# BaseShieldBrainDuino24Nov2017.net
KiCad netlist of a schematic drawn in EAGLE
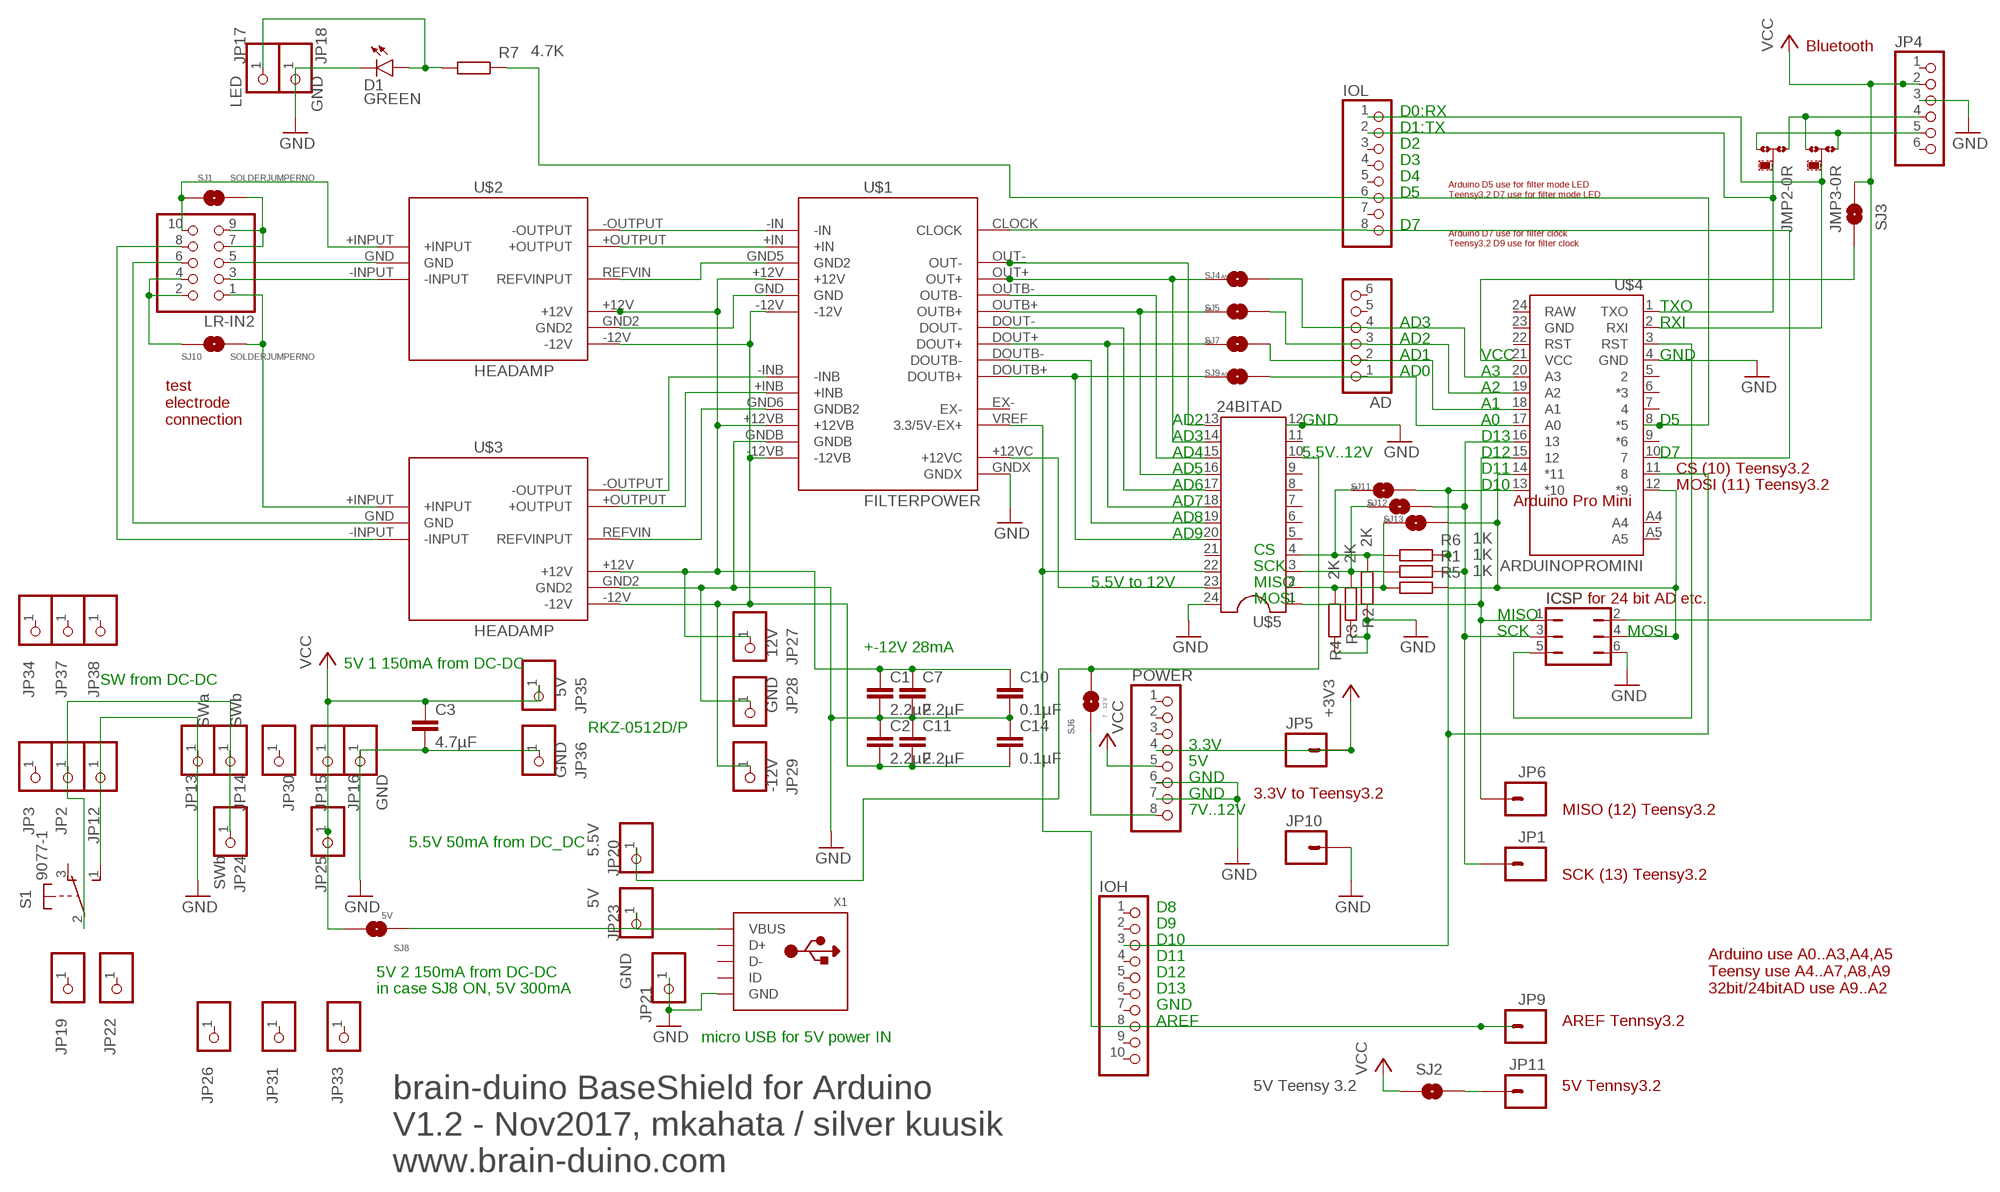
[diagram p0: schematic, sheet 1]

(export (version "E")
  (design (tool "Eeschema 10.0.6"))
  (components
    (comp (ref "AD")
      (value "PINHD-1X6")
      (footprint "eagle-import:1X06")
      (libsource (lib "eagle-import") (part "PINHD-1X6"))
    )
    (comp (ref "C1")
      (value "2.2µF")
      (footprint "eagle-import:C0402")
      (libsource (lib "eagle-import") (part "C-EUC0402"))
    )
    (comp (ref "C2")
      (value "2.2µF")
      (footprint "eagle-import:C0402")
      (libsource (lib "eagle-import") (part "C-EUC0402"))
    )
    (comp (ref "C3")
      (value "4.7µF")
      (footprint "eagle-import:C0402")
      (libsource (lib "eagle-import") (part "C-EUC0402"))
    )
    (comp (ref "C7")
      (value "2.2µF")
      (footprint "eagle-import:C0402")
      (libsource (lib "eagle-import") (part "C-EUC0402"))
    )
    (comp (ref "C10")
      (value "0.1µF")
      (footprint "eagle-import:C0402")
      (libsource (lib "eagle-import") (part "C-EUC0402"))
    )
    (comp (ref "C11")
      (value "2.2µF")
      (footprint "eagle-import:C0402")
      (libsource (lib "eagle-import") (part "C-EUC0402"))
    )
    (comp (ref "C14")
      (value "0.1µF")
      (footprint "eagle-import:C0402")
      (libsource (lib "eagle-import") (part "C-EUC0402"))
    )
    (comp (ref "D1")
      (value "GREEN")
      (footprint "eagle-import:LED-0603")
      (libsource (lib "eagle-import") (part "LED-GREEN0603"))
    )
    (comp (ref "ICSP")
      (value "JP3Q")
      (footprint "eagle-import:JP3Q")
      (libsource (lib "eagle-import") (part "JP3Q"))
    )
    (comp (ref "IOH")
      (value "PINHD-1X10")
      (footprint "eagle-import:1X10")
      (libsource (lib "eagle-import") (part "PINHD-1X10"))
    )
    (comp (ref "IOL")
      (value "PINHD-1X8")
      (footprint "eagle-import:1X08")
      (libsource (lib "eagle-import") (part "PINHD-1X8"))
    )
    (comp (ref "JMP2")
      (value "RX")
      (footprint "eagle-import:A0R-JMP")
      (libsource (lib "eagle-import") (part "0R-JUMPA"))
    )
    (comp (ref "JMP3")
      (value "TX")
      (footprint "eagle-import:A0R-JMP")
      (libsource (lib "eagle-import") (part "0R-JUMPA"))
    )
    (comp (ref "JP1")
      (value "M01PTH")
      (footprint "eagle-import:1X01")
      (libsource (lib "eagle-import") (part "M01PTH"))
    )
    (comp (ref "JP2")
      (value "PINHD-1X1")
      (footprint "eagle-import:1X01")
      (libsource (lib "eagle-import") (part "PINHD-1X1"))
    )
    (comp (ref "JP3")
      (value "PINHD-1X1")
      (footprint "eagle-import:1X01")
      (libsource (lib "eagle-import") (part "PINHD-1X1"))
    )
    (comp (ref "JP4")
      (value "PINHD-1X6")
      (footprint "eagle-import:1X06")
      (libsource (lib "eagle-import") (part "PINHD-1X6"))
    )
    (comp (ref "JP5")
      (value "M01PTH")
      (footprint "eagle-import:1X01")
      (libsource (lib "eagle-import") (part "M01PTH"))
    )
    (comp (ref "JP6")
      (value "M01PTH")
      (footprint "eagle-import:1X01")
      (libsource (lib "eagle-import") (part "M01PTH"))
    )
    (comp (ref "JP9")
      (value "M01PTH")
      (footprint "eagle-import:1X01")
      (libsource (lib "eagle-import") (part "M01PTH"))
    )
    (comp (ref "JP10")
      (value "M01PTH")
      (footprint "eagle-import:1X01")
      (libsource (lib "eagle-import") (part "M01PTH"))
    )
    (comp (ref "JP11")
      (value "M01PTH")
      (footprint "eagle-import:1X01")
      (libsource (lib "eagle-import") (part "M01PTH"))
    )
    (comp (ref "JP12")
      (value "PINHD-1X1")
      (footprint "eagle-import:1X01")
      (libsource (lib "eagle-import") (part "PINHD-1X1"))
    )
    (comp (ref "JP13")
      (value "SWa")
      (footprint "eagle-import:1X01")
      (libsource (lib "eagle-import") (part "PINHD-1X1"))
    )
    (comp (ref "JP14")
      (value "SWb")
      (footprint "eagle-import:1X01")
      (libsource (lib "eagle-import") (part "PINHD-1X1"))
    )
    (comp (ref "JP15")
      (value "+5V")
      (footprint "eagle-import:1X01")
      (libsource (lib "eagle-import") (part "PINHD-1X1"))
    )
    (comp (ref "JP16")
      (value "GND")
      (footprint "eagle-import:1X01")
      (libsource (lib "eagle-import") (part "PINHD-1X1"))
    )
    (comp (ref "JP17")
      (value "LED")
      (footprint "eagle-import:1X01")
      (libsource (lib "eagle-import") (part "PINHD-1X1"))
    )
    (comp (ref "JP18")
      (value "GND")
      (footprint "eagle-import:1X01")
      (libsource (lib "eagle-import") (part "PINHD-1X1"))
    )
    (comp (ref "JP19")
      (value "PINHD-1X1")
      (footprint "eagle-import:1X01")
      (libsource (lib "eagle-import") (part "PINHD-1X1"))
    )
    (comp (ref "JP20")
      (value "5.5V")
      (footprint "eagle-import:1X01")
      (libsource (lib "eagle-import") (part "PINHD-1X1"))
    )
    (comp (ref "JP21")
      (value "GND")
      (footprint "eagle-import:1X01")
      (libsource (lib "eagle-import") (part "PINHD-1X1"))
    )
    (comp (ref "JP22")
      (value "PINHD-1X1")
      (footprint "eagle-import:1X01")
      (libsource (lib "eagle-import") (part "PINHD-1X1"))
    )
    (comp (ref "JP23")
      (value "5V")
      (footprint "eagle-import:1X01")
      (libsource (lib "eagle-import") (part "PINHD-1X1"))
    )
    (comp (ref "JP24")
      (value "SWb")
      (footprint "eagle-import:1X01")
      (libsource (lib "eagle-import") (part "PINHD-1X1"))
    )
    (comp (ref "JP25")
      (value "+5V")
      (footprint "eagle-import:1X01")
      (libsource (lib "eagle-import") (part "PINHD-1X1"))
    )
    (comp (ref "JP26")
      (value "PINHD-1X1")
      (footprint "eagle-import:1X01")
      (libsource (lib "eagle-import") (part "PINHD-1X1"))
    )
    (comp (ref "JP27")
      (value "12V")
      (footprint "eagle-import:1X01")
      (libsource (lib "eagle-import") (part "PINHD-1X1"))
    )
    (comp (ref "JP28")
      (value "GND")
      (footprint "eagle-import:1X01")
      (libsource (lib "eagle-import") (part "PINHD-1X1"))
    )
    (comp (ref "JP29")
      (value "-12V")
      (footprint "eagle-import:1X01")
      (libsource (lib "eagle-import") (part "PINHD-1X1"))
    )
    (comp (ref "JP30")
      (value "PINHD-1X1")
      (footprint "eagle-import:1X01")
      (libsource (lib "eagle-import") (part "PINHD-1X1"))
    )
    (comp (ref "JP31")
      (value "PINHD-1X1")
      (footprint "eagle-import:1X01")
      (libsource (lib "eagle-import") (part "PINHD-1X1"))
    )
    (comp (ref "JP33")
      (value "PINHD-1X1")
      (footprint "eagle-import:1X01")
      (libsource (lib "eagle-import") (part "PINHD-1X1"))
    )
    (comp (ref "JP34")
      (value "PINHD-1X1")
      (footprint "eagle-import:1X01")
      (libsource (lib "eagle-import") (part "PINHD-1X1"))
    )
    (comp (ref "JP35")
      (value "5V")
      (footprint "eagle-import:1X01")
      (libsource (lib "eagle-import") (part "PINHD-1X1"))
    )
    (comp (ref "JP36")
      (value "GND")
      (footprint "eagle-import:1X01")
      (libsource (lib "eagle-import") (part "PINHD-1X1"))
    )
    (comp (ref "JP37")
      (value "PINHD-1X1")
      (footprint "eagle-import:1X01")
      (libsource (lib "eagle-import") (part "PINHD-1X1"))
    )
    (comp (ref "JP38")
      (value "PINHD-1X1")
      (footprint "eagle-import:1X01")
      (libsource (lib "eagle-import") (part "PINHD-1X1"))
    )
    (comp (ref "LR-IN2")
      (value "PINHD-2X5/90")
      (footprint "eagle-import:2X05_90")
      (libsource (lib "eagle-import") (part "PINHD-2X5/90"))
    )
    (comp (ref "POWER")
      (value "PINHD-1X8")
      (footprint "eagle-import:1X08")
      (libsource (lib "eagle-import") (part "PINHD-1X8"))
    )
    (comp (ref "R1")
      (value "1K")
      (footprint "eagle-import:R0402")
      (libsource (lib "eagle-import") (part "R-EU_R0402"))
    )
    (comp (ref "R2")
      (value "2K")
      (footprint "eagle-import:R0402")
      (libsource (lib "eagle-import") (part "R-EU_R0402"))
    )
    (comp (ref "R3")
      (value "2K")
      (footprint "eagle-import:R0402")
      (libsource (lib "eagle-import") (part "R-EU_R0402"))
    )
    (comp (ref "R4")
      (value "2K")
      (footprint "eagle-import:R0402")
      (libsource (lib "eagle-import") (part "R-EU_R0402"))
    )
    (comp (ref "R5")
      (value "1K")
      (footprint "eagle-import:R0402")
      (libsource (lib "eagle-import") (part "R-EU_R0402"))
    )
    (comp (ref "R6")
      (value "1K")
      (footprint "eagle-import:R0402")
      (libsource (lib "eagle-import") (part "R-EU_R0402"))
    )
    (comp (ref "R7")
      (value "4.7K")
      (footprint "eagle-import:R0402")
      (libsource (lib "eagle-import") (part "R-EU_R0402"))
    )
    (comp (ref "S1")
      (value "9077-1")
      (footprint "eagle-import:9077-1")
      (libsource (lib "eagle-import") (part "9077-1"))
    )
    (comp (ref "SJ1")
      (value "SOLDERJUMPERNO")
      (footprint "eagle-import:SJ_2S-NO")
      (libsource (lib "eagle-import") (part "SOLDERJUMPERNO"))
    )
    (comp (ref "SJ2")
      (value "5V Teensy 3.2")
      (footprint "eagle-import:SJ_2S-NO")
      (libsource (lib "eagle-import") (part "SOLDERJUMPERNO"))
    )
    (comp (ref "SJ3")
      (value "5V Arduino Pro Mini")
      (footprint "eagle-import:SJ_2S-NO")
      (libsource (lib "eagle-import") (part "SOLDERJUMPERNO"))
    )
    (comp (ref "SJ4")
      (value "A5")
      (footprint "eagle-import:SJ_2S-NO")
      (libsource (lib "eagle-import") (part "SOLDERJUMPERNO"))
    )
    (comp (ref "SJ5")
      (value "A4")
      (footprint "eagle-import:SJ_2S-NO")
      (libsource (lib "eagle-import") (part "SOLDERJUMPERNO"))
    )
    (comp (ref "SJ6")
      (value "7 .. 12 V")
      (footprint "eagle-import:SJ_2S-NO")
      (libsource (lib "eagle-import") (part "SOLDERJUMPERNO"))
    )
    (comp (ref "SJ7")
      (value "A2")
      (footprint "eagle-import:SJ_2S-NO")
      (libsource (lib "eagle-import") (part "SOLDERJUMPERNO"))
    )
    (comp (ref "SJ8")
      (value "5V")
      (footprint "eagle-import:SJ_2S-NO")
      (libsource (lib "eagle-import") (part "SOLDERJUMPERNO"))
    )
    (comp (ref "SJ9")
      (value "A0")
      (footprint "eagle-import:SJ_2S-NO")
      (libsource (lib "eagle-import") (part "SOLDERJUMPERNO"))
    )
    (comp (ref "SJ10")
      (value "SOLDERJUMPERNO")
      (footprint "eagle-import:SJ_2S-NO")
      (libsource (lib "eagle-import") (part "SOLDERJUMPERNO"))
    )
    (comp (ref "SJ11")
      (value "A4")
      (footprint "eagle-import:SJ_2S-NO")
      (libsource (lib "eagle-import") (part "SOLDERJUMPERNO"))
    )
    (comp (ref "SJ12")
      (value "A4")
      (footprint "eagle-import:SJ_2S-NO")
      (libsource (lib "eagle-import") (part "SOLDERJUMPERNO"))
    )
    (comp (ref "SJ13")
      (value "A4")
      (footprint "eagle-import:SJ_2S-NO")
      (libsource (lib "eagle-import") (part "SOLDERJUMPERNO"))
    )
    (comp (ref "U$1")
      (value "FILTERPOWER")
      (footprint "eagle-import:FILTERPOWER")
      (libsource (lib "eagle-import") (part "FILTERPOWER"))
    )
    (comp (ref "U$2")
      (value "HEADAMP")
      (footprint "eagle-import:HEADAMP")
      (libsource (lib "eagle-import") (part "HEADAMP"))
    )
    (comp (ref "U$3")
      (value "HEADAMP")
      (footprint "eagle-import:HEADAMP")
      (libsource (lib "eagle-import") (part "HEADAMP"))
    )
    (comp (ref "U$4")
      (value "ARDUINOPROMINI")
      (footprint "eagle-import:ARDUINOPROMINI")
      (libsource (lib "eagle-import") (part "ARDUINOPROMINI"))
    )
    (comp (ref "U$5")
      (value "24BITAD")
      (footprint "eagle-import:24BITAD")
      (libsource (lib "eagle-import") (part "24BITAD"))
    )
    (comp (ref "X1")
      (value "USB_MICRO_20329_V2")
      (footprint "eagle-import:4UCONN_20329_V2")
      (libsource (lib "eagle-import") (part "USB_MICRO_20329_V2"))
    )
  )
  (nets
    (net (code "1") (name "+3V3") (class "Default")
      (node (ref "JP5") (pin "1") (pinfunction "1_1") (pintype "passive"))
      (node (ref "POWER") (pin "4") (pinfunction "4_4") (pintype "passive"))
    )
    (net (code "2") (name "GND") (class "Default")
      (node (ref "C1") (pin "2") (pinfunction "2_2") (pintype "passive"))
      (node (ref "C10") (pin "2") (pinfunction "2_2") (pintype "passive"))
      (node (ref "C11") (pin "1") (pinfunction "1_1") (pintype "passive"))
      (node (ref "C14") (pin "1") (pinfunction "1_1") (pintype "passive"))
      (node (ref "C2") (pin "1") (pinfunction "1_1") (pintype "passive"))
      (node (ref "C3") (pin "2") (pinfunction "2_2") (pintype "passive"))
      (node (ref "C7") (pin "2") (pinfunction "2_2") (pintype "passive"))
      (node (ref "D1") (pin "C") (pinfunction "C_C") (pintype "passive"))
      (node (ref "ICSP") (pin "6") (pinfunction "6_6") (pintype "passive"))
      (node (ref "JP10") (pin "1") (pinfunction "1_1") (pintype "passive"))
      (node (ref "JP12") (pin "1") (pinfunction "1_1") (pintype "passive"))
      (node (ref "JP13") (pin "1") (pinfunction "1_1") (pintype "passive"))
      (node (ref "JP16") (pin "1") (pinfunction "1_1") (pintype "passive"))
      (node (ref "JP18") (pin "1") (pinfunction "1_1") (pintype "passive"))
      (node (ref "JP21") (pin "1") (pinfunction "1_1") (pintype "passive"))
      (node (ref "JP28") (pin "1") (pinfunction "1_1") (pintype "passive"))
      (node (ref "JP36") (pin "1") (pinfunction "1_1") (pintype "passive"))
      (node (ref "JP4") (pin "3") (pinfunction "3_3") (pintype "passive"))
      (node (ref "POWER") (pin "6") (pinfunction "6_6") (pintype "passive"))
      (node (ref "POWER") (pin "7") (pinfunction "7_7") (pintype "passive"))
      (node (ref "R2") (pin "1") (pinfunction "1_1") (pintype "passive"))
      (node (ref "R3") (pin "1") (pinfunction "1_1") (pintype "passive"))
      (node (ref "R4") (pin "1") (pinfunction "1_1") (pintype "passive"))
      (node (ref "S1") (pin "1") (pinfunction "S_1") (pintype "passive"))
      (node (ref "U$1") (pin "GNDB") (pinfunction "GNDB_GNDB") (pintype "power_in"))
      (node (ref "U$1") (pin "GNDX") (pinfunction "GNDX_GNDX") (pintype "power_in"))
      (node (ref "U$3") (pin "GND2") (pinfunction "GND2_GND2") (pintype "bidirectional"))
      (node (ref "U$4") (pin "4") (pinfunction "GND_4") (pintype "bidirectional"))
      (node (ref "U$5") (pin "12") (pinfunction "12_12") (pintype "passive"))
      (node (ref "U$5") (pin "24") (pinfunction "24_24") (pintype "passive"))
      (node (ref "X1") (pin "BASE@1") (pinfunction "GND_BASE@1") (pintype "power_in"))
      (node (ref "X1") (pin "BASE@2") (pinfunction "GND_BASE@2") (pintype "power_in"))
      (node (ref "X1") (pin "GND") (pinfunction "GND_GND") (pintype "power_in"))
      (node (ref "X1") (pin "SPRT@1") (pinfunction "GND_SPRT@1") (pintype "power_in"))
      (node (ref "X1") (pin "SPRT@2") (pinfunction "GND_SPRT@2") (pintype "power_in"))
      (node (ref "X1") (pin "SPRT@3") (pinfunction "GND_SPRT@3") (pintype "power_in"))
      (node (ref "X1") (pin "SPRT@4") (pinfunction "GND_SPRT@4") (pintype "power_in"))
    )
    (net (code "3") (name "Net-(C1-Pad1)") (class "Default")
      (node (ref "C1") (pin "1") (pinfunction "1_1") (pintype "passive"))
      (node (ref "C10") (pin "1") (pinfunction "1_1") (pintype "passive"))
      (node (ref "C7") (pin "1") (pinfunction "1_1") (pintype "passive"))
      (node (ref "JP27") (pin "1") (pinfunction "1_1") (pintype "passive"))
      (node (ref "U$1") (pin "+12V") (pinfunction "+12V_+12V") (pintype "bidirectional"))
      (node (ref "U$1") (pin "+12VB") (pinfunction "+12VB_+12VB") (pintype "bidirectional"))
      (node (ref "U$2") (pin "+12V") (pinfunction "+12V_+12V") (pintype "bidirectional"))
      (node (ref "U$3") (pin "+12V") (pinfunction "+12V_+12V") (pintype "bidirectional"))
    )
    (net (code "4") (name "Net-(C11-Pad2)") (class "Default")
      (node (ref "C11") (pin "2") (pinfunction "2_2") (pintype "passive"))
      (node (ref "C14") (pin "2") (pinfunction "2_2") (pintype "passive"))
      (node (ref "C2") (pin "2") (pinfunction "2_2") (pintype "passive"))
      (node (ref "JP29") (pin "1") (pinfunction "1_1") (pintype "passive"))
      (node (ref "U$1") (pin "-12V") (pinfunction "-12V_-12V") (pintype "bidirectional"))
      (node (ref "U$1") (pin "-12VB") (pinfunction "-12VB_-12VB") (pintype "bidirectional"))
      (node (ref "U$2") (pin "-12V") (pinfunction "-12V_-12V") (pintype "bidirectional"))
      (node (ref "U$3") (pin "-12V") (pinfunction "-12V_-12V") (pintype "bidirectional"))
    )
    (net (code "5") (name "Net-(D1-PadA)") (class "Default")
      (node (ref "D1") (pin "A") (pinfunction "A_A") (pintype "passive"))
      (node (ref "JP17") (pin "1") (pinfunction "1_1") (pintype "passive"))
      (node (ref "R7") (pin "1") (pinfunction "1_1") (pintype "passive"))
    )
    (net (code "6") (name "Net-(ICSP-Pad5)") (class "Default")
      (node (ref "ICSP") (pin "5") (pinfunction "5_5") (pintype "passive"))
      (node (ref "U$4") (pin "3") (pinfunction "RST_3") (pintype "bidirectional"))
    )
    (net (code "7") (name "Net-(JMP2-Pad1)") (class "Default")
      (node (ref "JMP2") (pin "1") (pinfunction "1_1") (pintype "passive"))
      (node (ref "JMP3") (pin "3") (pinfunction "3_3") (pintype "passive"))
      (node (ref "JP4") (pin "4") (pinfunction "4_4") (pintype "passive"))
    )
    (net (code "8") (name "Net-(JMP2-Pad3)") (class "Default")
      (node (ref "JMP2") (pin "3") (pinfunction "3_3") (pintype "passive"))
      (node (ref "JMP3") (pin "1") (pinfunction "1_1") (pintype "passive"))
      (node (ref "JP4") (pin "5") (pinfunction "5_5") (pintype "passive"))
    )
    (net (code "9") (name "Net-(JP11-Pad1)") (class "Default")
      (node (ref "JP11") (pin "1") (pinfunction "1_1") (pintype "passive"))
      (node (ref "SJ2") (pin "2") (pinfunction "2_2") (pintype "passive"))
    )
    (net (code "10") (name "Net-(JP20-Pad1)") (class "Default")
      (node (ref "JP20") (pin "1") (pinfunction "1_1") (pintype "passive"))
      (node (ref "SJ6") (pin "2") (pinfunction "2_2") (pintype "passive"))
      (node (ref "U$5") (pin "10") (pinfunction "10_10") (pintype "passive"))
    )
    (net (code "11") (name "Net-(JP23-Pad1)") (class "Default")
      (node (ref "JP23") (pin "1") (pinfunction "1_1") (pintype "passive"))
      (node (ref "SJ8") (pin "1") (pinfunction "1_1") (pintype "passive"))
      (node (ref "X1") (pin "VBUS") (pinfunction "VBUS_VBUS") (pintype "power_in"))
    )
    (net (code "12") (name "Net-(LR-IN2-Pad1)") (class "Default")
      (node (ref "LR-IN2") (pin "1") (pinfunction "1_1") (pintype "passive"))
      (node (ref "SJ10") (pin "2") (pinfunction "2_2") (pintype "passive"))
      (node (ref "U$3") (pin "+INPUT") (pinfunction "+INPUT_+INPUT") (pintype "bidirectional"))
    )
    (net (code "13") (name "Net-(LR-IN2-Pad2)") (class "Default")
      (node (ref "LR-IN2") (pin "2") (pinfunction "2_2") (pintype "passive"))
      (node (ref "LR-IN2") (pin "4") (pinfunction "4_4") (pintype "passive"))
      (node (ref "SJ10") (pin "1") (pinfunction "1_1") (pintype "passive"))
    )
    (net (code "14") (name "Net-(LR-IN2-Pad3)") (class "Default")
      (node (ref "LR-IN2") (pin "3") (pinfunction "3_3") (pintype "passive"))
      (node (ref "U$2") (pin "-INPUT") (pinfunction "-INPUT_-INPUT") (pintype "bidirectional"))
    )
    (net (code "15") (name "Net-(LR-IN2-Pad5)") (class "Default")
      (node (ref "LR-IN2") (pin "5") (pinfunction "5_5") (pintype "passive"))
      (node (ref "U$2") (pin "GND") (pinfunction "GND_GND") (pintype "bidirectional"))
    )
    (net (code "16") (name "Net-(LR-IN2-Pad6)") (class "Default")
      (node (ref "LR-IN2") (pin "6") (pinfunction "6_6") (pintype "passive"))
      (node (ref "U$3") (pin "GND") (pinfunction "GND_GND") (pintype "bidirectional"))
    )
    (net (code "17") (name "Net-(LR-IN2-Pad7)") (class "Default")
      (node (ref "LR-IN2") (pin "7") (pinfunction "7_7") (pintype "passive"))
      (node (ref "LR-IN2") (pin "9") (pinfunction "9_9") (pintype "passive"))
      (node (ref "SJ1") (pin "2") (pinfunction "2_2") (pintype "passive"))
    )
    (net (code "18") (name "Net-(LR-IN2-Pad8)") (class "Default")
      (node (ref "LR-IN2") (pin "8") (pinfunction "8_8") (pintype "passive"))
      (node (ref "U$3") (pin "-INPUT") (pinfunction "-INPUT_-INPUT") (pintype "bidirectional"))
    )
    (net (code "19") (name "Net-(LR-IN2-Pad10)") (class "Default")
      (node (ref "LR-IN2") (pin "10") (pinfunction "10_10") (pintype "passive"))
      (node (ref "SJ1") (pin "1") (pinfunction "1_1") (pintype "passive"))
      (node (ref "U$2") (pin "+INPUT") (pinfunction "+INPUT_+INPUT") (pintype "bidirectional"))
    )
    (net (code "20") (name "Net-(POWER-Pad8)") (class "Default")
      (node (ref "POWER") (pin "8") (pinfunction "8_8") (pintype "passive"))
      (node (ref "SJ6") (pin "1") (pinfunction "1_1") (pintype "passive"))
    )
    (net (code "21") (name "Net-(R1-Pad1)") (class "Default")
      (node (ref "R1") (pin "1") (pinfunction "1_1") (pintype "passive"))
      (node (ref "R3") (pin "2") (pinfunction "2_2") (pintype "passive"))
      (node (ref "SJ12") (pin "1") (pinfunction "1_1") (pintype "passive"))
      (node (ref "U$5") (pin "3") (pinfunction "3_3") (pintype "passive"))
    )
    (net (code "22") (name "Net-(R2-Pad2)") (class "Default")
      (node (ref "R2") (pin "2") (pinfunction "2_2") (pintype "passive"))
      (node (ref "R6") (pin "1") (pinfunction "1_1") (pintype "passive"))
      (node (ref "SJ11") (pin "1") (pinfunction "1_1") (pintype "passive"))
      (node (ref "U$5") (pin "4") (pinfunction "4_4") (pintype "passive"))
    )
    (net (code "23") (name "Net-(R4-Pad2)") (class "Default")
      (node (ref "R4") (pin "2") (pinfunction "2_2") (pintype "passive"))
      (node (ref "R5") (pin "1") (pinfunction "1_1") (pintype "passive"))
      (node (ref "SJ13") (pin "1") (pinfunction "1_1") (pintype "passive"))
      (node (ref "U$5") (pin "2") (pinfunction "2_2") (pintype "passive"))
    )
    (net (code "24") (name "Net-(S1-P)") (class "Default")
      (node (ref "JP14") (pin "1") (pinfunction "1_1") (pintype "passive"))
      (node (ref "JP2") (pin "1") (pinfunction "1_1") (pintype "passive"))
      (node (ref "JP24") (pin "1") (pinfunction "1_1") (pintype "passive"))
      (node (ref "S1") (pin "2") (pinfunction "P_2") (pintype "passive"))
    )
    (net (code "25") (name "Net-(SJ4-Pad1)") (class "Default")
      (node (ref "SJ4") (pin "1") (pinfunction "1_1") (pintype "passive"))
      (node (ref "U$1") (pin "OUT+") (pinfunction "OUT+_OUT+") (pintype "power_in"))
      (node (ref "U$5") (pin "14") (pinfunction "14_14") (pintype "passive"))
    )
    (net (code "26") (name "Net-(SJ5-Pad1)") (class "Default")
      (node (ref "SJ5") (pin "1") (pinfunction "1_1") (pintype "passive"))
      (node (ref "U$1") (pin "OUTB+") (pinfunction "OUTB+_OUTB+") (pintype "power_in"))
      (node (ref "U$5") (pin "16") (pinfunction "16_16") (pintype "passive"))
    )
    (net (code "27") (name "Net-(SJ7-Pad1)") (class "Default")
      (node (ref "SJ7") (pin "1") (pinfunction "1_1") (pintype "passive"))
      (node (ref "U$1") (pin "DOUT+") (pinfunction "DOUT+_DOUT+") (pintype "output"))
      (node (ref "U$5") (pin "18") (pinfunction "18_18") (pintype "passive"))
    )
    (net (code "28") (name "Net-(SJ9-Pad1)") (class "Default")
      (node (ref "SJ9") (pin "1") (pinfunction "1_1") (pintype "passive"))
      (node (ref "U$1") (pin "DOUTB+") (pinfunction "DOUTB+_DOUTB+") (pintype "output"))
      (node (ref "U$5") (pin "20") (pinfunction "20_20") (pintype "passive"))
    )
    (net (code "29") (name "Net-(U$1-3.3{slash}5V-EX+)") (class "Default")
      (node (ref "IOH") (pin "8") (pinfunction "8_8") (pintype "passive"))
      (node (ref "JP9") (pin "1") (pinfunction "1_1") (pintype "passive"))
      (node (ref "U$1") (pin "VREF") (pinfunction "3.3/5V-EX+_VREF") (pintype "output"))
      (node (ref "U$5") (pin "22") (pinfunction "22_22") (pintype "passive"))
    )
    (net (code "30") (name "Net-(U$1-GND2)") (class "Default")
      (node (ref "U$1") (pin "GND5") (pinfunction "GND2_GND5") (pintype "power_in"))
      (node (ref "U$2") (pin "REFVIN") (pinfunction "REFVINPUT_REFVIN") (pintype "bidirectional"))
    )
    (net (code "31") (name "Net-(U$1-GNDB2)") (class "Default")
      (node (ref "U$1") (pin "GND6") (pinfunction "GNDB2_GND6") (pintype "power_in"))
      (node (ref "U$3") (pin "REFVIN") (pinfunction "REFVINPUT_REFVIN") (pintype "bidirectional"))
    )
    (net (code "32") (name "Net-(U$1-Pad+12VC)") (class "Default")
      (node (ref "U$1") (pin "+12VC") (pinfunction "+12VC_+12VC") (pintype "power_in"))
      (node (ref "U$5") (pin "23") (pinfunction "23_23") (pintype "passive"))
    )
    (net (code "33") (name "Net-(U$1-Pad+IN)") (class "Default")
      (node (ref "U$1") (pin "+IN") (pinfunction "+IN_+IN") (pintype "input"))
      (node (ref "U$2") (pin "+OUTPUT") (pinfunction "+OUTPUT_+OUTPUT") (pintype "bidirectional"))
    )
    (net (code "34") (name "Net-(U$1-Pad+INB)") (class "Default")
      (node (ref "U$1") (pin "+INB") (pinfunction "+INB_+INB") (pintype "bidirectional"))
      (node (ref "U$3") (pin "+OUTPUT") (pinfunction "+OUTPUT_+OUTPUT") (pintype "bidirectional"))
    )
    (net (code "35") (name "Net-(U$1-Pad-IN)") (class "Default")
      (node (ref "U$1") (pin "-IN") (pinfunction "-IN_-IN") (pintype "input"))
      (node (ref "U$2") (pin "-OUTPUT") (pinfunction "-OUTPUT_-OUTPUT") (pintype "bidirectional"))
    )
    (net (code "36") (name "Net-(U$1-Pad-INB)") (class "Default")
      (node (ref "U$1") (pin "-INB") (pinfunction "-INB_-INB") (pintype "bidirectional"))
      (node (ref "U$3") (pin "-OUTPUT") (pinfunction "-OUTPUT_-OUTPUT") (pintype "bidirectional"))
    )
    (net (code "37") (name "Net-(U$1-PadDOUT-)") (class "Default")
      (node (ref "U$1") (pin "DOUT-") (pinfunction "DOUT-_DOUT-") (pintype "output"))
      (node (ref "U$5") (pin "17") (pinfunction "17_17") (pintype "passive"))
    )
    (net (code "38") (name "Net-(U$1-PadDOUTB-)") (class "Default")
      (node (ref "U$1") (pin "DOUTB-") (pinfunction "DOUTB-_DOUTB-") (pintype "output"))
      (node (ref "U$5") (pin "19") (pinfunction "19_19") (pintype "passive"))
    )
    (net (code "39") (name "Net-(U$1-PadGND)") (class "Default")
      (node (ref "U$1") (pin "GND") (pinfunction "GND_GND") (pintype "power_in"))
      (node (ref "U$2") (pin "GND2") (pinfunction "GND2_GND2") (pintype "bidirectional"))
    )
    (net (code "40") (name "Net-(U$1-PadOUT-)") (class "Default")
      (node (ref "U$1") (pin "OUT-") (pinfunction "OUT-_OUT-") (pintype "bidirectional"))
      (node (ref "U$5") (pin "13") (pinfunction "13_13") (pintype "passive"))
    )
    (net (code "41") (name "Net-(U$1-PadOUTB-)") (class "Default")
      (node (ref "U$1") (pin "OUTB-") (pinfunction "OUTB-_OUTB-") (pintype "output"))
      (node (ref "U$5") (pin "15") (pinfunction "15_15") (pintype "passive"))
    )
    (net (code "42") (name "Net-(U$4-*5)") (class "Default")
      (node (ref "IOL") (pin "6") (pinfunction "6_6") (pintype "passive"))
      (node (ref "R7") (pin "2") (pinfunction "2_2") (pintype "passive"))
      (node (ref "U$4") (pin "8") (pinfunction "*5_8") (pintype "bidirectional"))
    )
    (net (code "43") (name "Net-(U$4-*10)") (class "Default")
      (node (ref "IOH") (pin "3") (pinfunction "3_3") (pintype "passive"))
      (node (ref "R6") (pin "2") (pinfunction "2_2") (pintype "passive"))
      (node (ref "SJ11") (pin "2") (pinfunction "2_2") (pintype "passive"))
      (node (ref "U$4") (pin "11") (pinfunction "8_11") (pintype "bidirectional"))
      (node (ref "U$4") (pin "13") (pinfunction "*10_13") (pintype "bidirectional"))
    )
    (net (code "44") (name "Net-(U$4-*11)") (class "Default")
      (node (ref "ICSP") (pin "4") (pinfunction "4_4") (pintype "passive"))
      (node (ref "R5") (pin "2") (pinfunction "2_2") (pintype "passive"))
      (node (ref "SJ13") (pin "2") (pinfunction "2_2") (pintype "passive"))
      (node (ref "U$4") (pin "12") (pinfunction "*9_12") (pintype "bidirectional"))
      (node (ref "U$4") (pin "14") (pinfunction "*11_14") (pintype "bidirectional"))
    )
    (net (code "45") (name "Net-(U$4-7)") (class "Default")
      (node (ref "IOL") (pin "8") (pinfunction "8_8") (pintype "passive"))
      (node (ref "U$1") (pin "CLOCK") (pinfunction "CLOCK_CLOCK") (pintype "input"))
      (node (ref "U$4") (pin "10") (pinfunction "7_10") (pintype "bidirectional"))
    )
    (net (code "46") (name "Net-(U$4-12)") (class "Default")
      (node (ref "ICSP") (pin "1") (pinfunction "1_1") (pintype "passive"))
      (node (ref "JP6") (pin "1") (pinfunction "1_1") (pintype "passive"))
      (node (ref "U$4") (pin "15") (pinfunction "12_15") (pintype "bidirectional"))
      (node (ref "U$5") (pin "1") (pinfunction "1_1") (pintype "passive"))
    )
    (net (code "47") (name "Net-(U$4-13)") (class "Default")
      (node (ref "ICSP") (pin "3") (pinfunction "3_3") (pintype "passive"))
      (node (ref "JP1") (pin "1") (pinfunction "1_1") (pintype "passive"))
      (node (ref "R1") (pin "2") (pinfunction "2_2") (pintype "passive"))
      (node (ref "SJ12") (pin "2") (pinfunction "2_2") (pintype "passive"))
      (node (ref "U$4") (pin "16") (pinfunction "13_16") (pintype "bidirectional"))
    )
    (net (code "48") (name "Net-(U$4-A0)") (class "Default")
      (node (ref "AD") (pin "1") (pinfunction "1_1") (pintype "passive"))
      (node (ref "SJ9") (pin "2") (pinfunction "2_2") (pintype "passive"))
      (node (ref "U$4") (pin "17") (pinfunction "A0_17") (pintype "bidirectional"))
    )
    (net (code "49") (name "Net-(U$4-A1)") (class "Default")
      (node (ref "AD") (pin "2") (pinfunction "2_2") (pintype "passive"))
      (node (ref "SJ7") (pin "2") (pinfunction "2_2") (pintype "passive"))
      (node (ref "U$4") (pin "18") (pinfunction "A1_18") (pintype "bidirectional"))
    )
    (net (code "50") (name "Net-(U$4-A2)") (class "Default")
      (node (ref "AD") (pin "3") (pinfunction "3_3") (pintype "passive"))
      (node (ref "SJ5") (pin "2") (pinfunction "2_2") (pintype "passive"))
      (node (ref "U$4") (pin "19") (pinfunction "A2_19") (pintype "bidirectional"))
    )
    (net (code "51") (name "Net-(U$4-A3)") (class "Default")
      (node (ref "AD") (pin "4") (pinfunction "4_4") (pintype "passive"))
      (node (ref "SJ4") (pin "2") (pinfunction "2_2") (pintype "passive"))
      (node (ref "U$4") (pin "20") (pinfunction "A3_20") (pintype "bidirectional"))
    )
    (net (code "52") (name "Net-(U$4-RXI)") (class "Default")
      (node (ref "IOL") (pin "1") (pinfunction "1_1") (pintype "passive"))
      (node (ref "JMP3") (pin "2") (pinfunction "2_2") (pintype "passive"))
      (node (ref "U$4") (pin "2") (pinfunction "RXI_2") (pintype "bidirectional"))
    )
    (net (code "53") (name "Net-(U$4-TXO)") (class "Default")
      (node (ref "IOL") (pin "2") (pinfunction "2_2") (pintype "passive"))
      (node (ref "JMP2") (pin "2") (pinfunction "2_2") (pintype "passive"))
      (node (ref "U$4") (pin "1") (pinfunction "TXO_1") (pintype "bidirectional"))
    )
    (net (code "54") (name "Net-(U$4-VCC)") (class "Default")
      (node (ref "SJ3") (pin "1") (pinfunction "1_1") (pintype "passive"))
      (node (ref "U$4") (pin "21") (pinfunction "VCC_21") (pintype "bidirectional"))
    )
    (net (code "55") (name "VCC") (class "Default")
      (node (ref "C3") (pin "1") (pinfunction "1_1") (pintype "passive"))
      (node (ref "ICSP") (pin "2") (pinfunction "2_2") (pintype "passive"))
      (node (ref "JP15") (pin "1") (pinfunction "1_1") (pintype "passive"))
      (node (ref "JP25") (pin "1") (pinfunction "1_1") (pintype "passive"))
      (node (ref "JP35") (pin "1") (pinfunction "1_1") (pintype "passive"))
      (node (ref "JP4") (pin "2") (pinfunction "2_2") (pintype "passive"))
      (node (ref "POWER") (pin "5") (pinfunction "5_5") (pintype "passive"))
      (node (ref "SJ2") (pin "1") (pinfunction "1_1") (pintype "passive"))
      (node (ref "SJ3") (pin "2") (pinfunction "2_2") (pintype "passive"))
      (node (ref "SJ8") (pin "2") (pinfunction "2_2") (pintype "passive"))
    )
    (net (code "56") (name "unconnected-(AD-Pad5)") (class "Default")
      (node (ref "AD") (pin "5") (pinfunction "5_5") (pintype "passive"))
    )
    (net (code "57") (name "unconnected-(AD-Pad6)") (class "Default")
      (node (ref "AD") (pin "6") (pinfunction "6_6") (pintype "passive"))
    )
    (net (code "58") (name "unconnected-(IOH-Pad1)") (class "Default")
      (node (ref "IOH") (pin "1") (pinfunction "1_1") (pintype "passive"))
    )
    (net (code "59") (name "unconnected-(IOH-Pad2)") (class "Default")
      (node (ref "IOH") (pin "2") (pinfunction "2_2") (pintype "passive"))
    )
    (net (code "60") (name "unconnected-(IOH-Pad4)") (class "Default")
      (node (ref "IOH") (pin "4") (pinfunction "4_4") (pintype "passive"))
    )
    (net (code "61") (name "unconnected-(IOH-Pad5)") (class "Default")
      (node (ref "IOH") (pin "5") (pinfunction "5_5") (pintype "passive"))
    )
    (net (code "62") (name "unconnected-(IOH-Pad6)") (class "Default")
      (node (ref "IOH") (pin "6") (pinfunction "6_6") (pintype "passive"))
    )
    (net (code "63") (name "unconnected-(IOH-Pad7)") (class "Default")
      (node (ref "IOH") (pin "7") (pinfunction "7_7") (pintype "passive"))
    )
    (net (code "64") (name "unconnected-(IOH-Pad9)") (class "Default")
      (node (ref "IOH") (pin "9") (pinfunction "9_9") (pintype "passive"))
    )
    (net (code "65") (name "unconnected-(IOH-Pad10)") (class "Default")
      (node (ref "IOH") (pin "10") (pinfunction "10_10") (pintype "passive"))
    )
    (net (code "66") (name "unconnected-(IOL-Pad3)") (class "Default")
      (node (ref "IOL") (pin "3") (pinfunction "3_3") (pintype "passive"))
    )
    (net (code "67") (name "unconnected-(IOL-Pad4)") (class "Default")
      (node (ref "IOL") (pin "4") (pinfunction "4_4") (pintype "passive"))
    )
    (net (code "68") (name "unconnected-(IOL-Pad5)") (class "Default")
      (node (ref "IOL") (pin "5") (pinfunction "5_5") (pintype "passive"))
    )
    (net (code "69") (name "unconnected-(IOL-Pad7)") (class "Default")
      (node (ref "IOL") (pin "7") (pinfunction "7_7") (pintype "passive"))
    )
    (net (code "70") (name "unconnected-(JP3-Pad1)") (class "Default")
      (node (ref "JP3") (pin "1") (pinfunction "1_1") (pintype "passive"))
    )
    (net (code "71") (name "unconnected-(JP4-Pad1)") (class "Default")
      (node (ref "JP4") (pin "1") (pinfunction "1_1") (pintype "passive"))
    )
    (net (code "72") (name "unconnected-(JP4-Pad6)") (class "Default")
      (node (ref "JP4") (pin "6") (pinfunction "6_6") (pintype "passive"))
    )
    (net (code "73") (name "unconnected-(JP19-Pad1)") (class "Default")
      (node (ref "JP19") (pin "1") (pinfunction "1_1") (pintype "passive"))
    )
    (net (code "74") (name "unconnected-(JP22-Pad1)") (class "Default")
      (node (ref "JP22") (pin "1") (pinfunction "1_1") (pintype "passive"))
    )
    (net (code "75") (name "unconnected-(JP26-Pad1)") (class "Default")
      (node (ref "JP26") (pin "1") (pinfunction "1_1") (pintype "passive"))
    )
    (net (code "76") (name "unconnected-(JP30-Pad1)") (class "Default")
      (node (ref "JP30") (pin "1") (pinfunction "1_1") (pintype "passive"))
    )
    (net (code "77") (name "unconnected-(JP31-Pad1)") (class "Default")
      (node (ref "JP31") (pin "1") (pinfunction "1_1") (pintype "passive"))
    )
    (net (code "78") (name "unconnected-(JP33-Pad1)") (class "Default")
      (node (ref "JP33") (pin "1") (pinfunction "1_1") (pintype "passive"))
    )
    (net (code "79") (name "unconnected-(JP34-Pad1)") (class "Default")
      (node (ref "JP34") (pin "1") (pinfunction "1_1") (pintype "passive"))
    )
    (net (code "80") (name "unconnected-(JP37-Pad1)") (class "Default")
      (node (ref "JP37") (pin "1") (pinfunction "1_1") (pintype "passive"))
    )
    (net (code "81") (name "unconnected-(JP38-Pad1)") (class "Default")
      (node (ref "JP38") (pin "1") (pinfunction "1_1") (pintype "passive"))
    )
    (net (code "82") (name "unconnected-(POWER-Pad1)") (class "Default")
      (node (ref "POWER") (pin "1") (pinfunction "1_1") (pintype "passive"))
    )
    (net (code "83") (name "unconnected-(POWER-Pad2)") (class "Default")
      (node (ref "POWER") (pin "2") (pinfunction "2_2") (pintype "passive"))
    )
    (net (code "84") (name "unconnected-(POWER-Pad3)") (class "Default")
      (node (ref "POWER") (pin "3") (pinfunction "3_3") (pintype "passive"))
    )
    (net (code "85") (name "unconnected-(S1-O-Pad3)") (class "Default")
      (node (ref "S1") (pin "3") (pinfunction "O_3") (pintype "passive"))
    )
    (net (code "86") (name "unconnected-(U$1-PadEX-)") (class "Default")
      (node (ref "U$1") (pin "EX-") (pinfunction "EX-_EX-") (pintype "output"))
    )
    (net (code "87") (name "unconnected-(U$4-*3-Pad6)") (class "Default")
      (node (ref "U$4") (pin "6") (pinfunction "*3_6") (pintype "bidirectional"))
    )
    (net (code "88") (name "unconnected-(U$4-*6-Pad9)") (class "Default")
      (node (ref "U$4") (pin "9") (pinfunction "*6_9") (pintype "bidirectional"))
    )
    (net (code "89") (name "unconnected-(U$4-2-Pad5)") (class "Default")
      (node (ref "U$4") (pin "5") (pinfunction "2_5") (pintype "bidirectional"))
    )
    (net (code "90") (name "unconnected-(U$4-4-Pad7)") (class "Default")
      (node (ref "U$4") (pin "7") (pinfunction "4_7") (pintype "bidirectional"))
    )
    (net (code "91") (name "unconnected-(U$4-GND-Pad23)") (class "Default")
      (node (ref "U$4") (pin "23") (pinfunction "GND_23") (pintype "bidirectional"))
    )
    (net (code "92") (name "unconnected-(U$4-PadA4)") (class "Default")
      (node (ref "U$4") (pin "A4") (pinfunction "A4_A4") (pintype "bidirectional"))
    )
    (net (code "93") (name "unconnected-(U$4-PadA5)") (class "Default")
      (node (ref "U$4") (pin "A5") (pinfunction "A5_A5") (pintype "bidirectional"))
    )
    (net (code "94") (name "unconnected-(U$4-RAW-Pad24)") (class "Default")
      (node (ref "U$4") (pin "24") (pinfunction "RAW_24") (pintype "bidirectional"))
    )
    (net (code "95") (name "unconnected-(U$4-RST-Pad22)") (class "Default")
      (node (ref "U$4") (pin "22") (pinfunction "RST_22") (pintype "bidirectional"))
    )
    (net (code "96") (name "unconnected-(U$5-Pad5)") (class "Default")
      (node (ref "U$5") (pin "5") (pinfunction "5_5") (pintype "passive"))
    )
    (net (code "97") (name "unconnected-(U$5-Pad6)") (class "Default")
      (node (ref "U$5") (pin "6") (pinfunction "6_6") (pintype "passive"))
    )
    (net (code "98") (name "unconnected-(U$5-Pad7)") (class "Default")
      (node (ref "U$5") (pin "7") (pinfunction "7_7") (pintype "passive"))
    )
    (net (code "99") (name "unconnected-(U$5-Pad8)") (class "Default")
      (node (ref "U$5") (pin "8") (pinfunction "8_8") (pintype "passive"))
    )
    (net (code "100") (name "unconnected-(U$5-Pad9)") (class "Default")
      (node (ref "U$5") (pin "9") (pinfunction "9_9") (pintype "passive"))
    )
    (net (code "101") (name "unconnected-(U$5-Pad11)") (class "Default")
      (node (ref "U$5") (pin "11") (pinfunction "11_11") (pintype "passive"))
    )
    (net (code "102") (name "unconnected-(U$5-Pad21)") (class "Default")
      (node (ref "U$5") (pin "21") (pinfunction "21_21") (pintype "passive"))
    )
    (net (code "103") (name "unconnected-(X1-PadD+)") (class "Default")
      (node (ref "X1") (pin "D+") (pinfunction "D+_D+") (pintype "bidirectional"))
    )
    (net (code "104") (name "unconnected-(X1-PadD-)") (class "Default")
      (node (ref "X1") (pin "D-") (pinfunction "D-_D-") (pintype "bidirectional"))
    )
    (net (code "105") (name "unconnected-(X1-PadID)") (class "Default")
      (node (ref "X1") (pin "ID") (pinfunction "ID_ID") (pintype "bidirectional"))
    )
  )
)
